# NES_IO_US_NOCUT_REV1_5.net
KiCad netlist of a schematic drawn in EAGLE
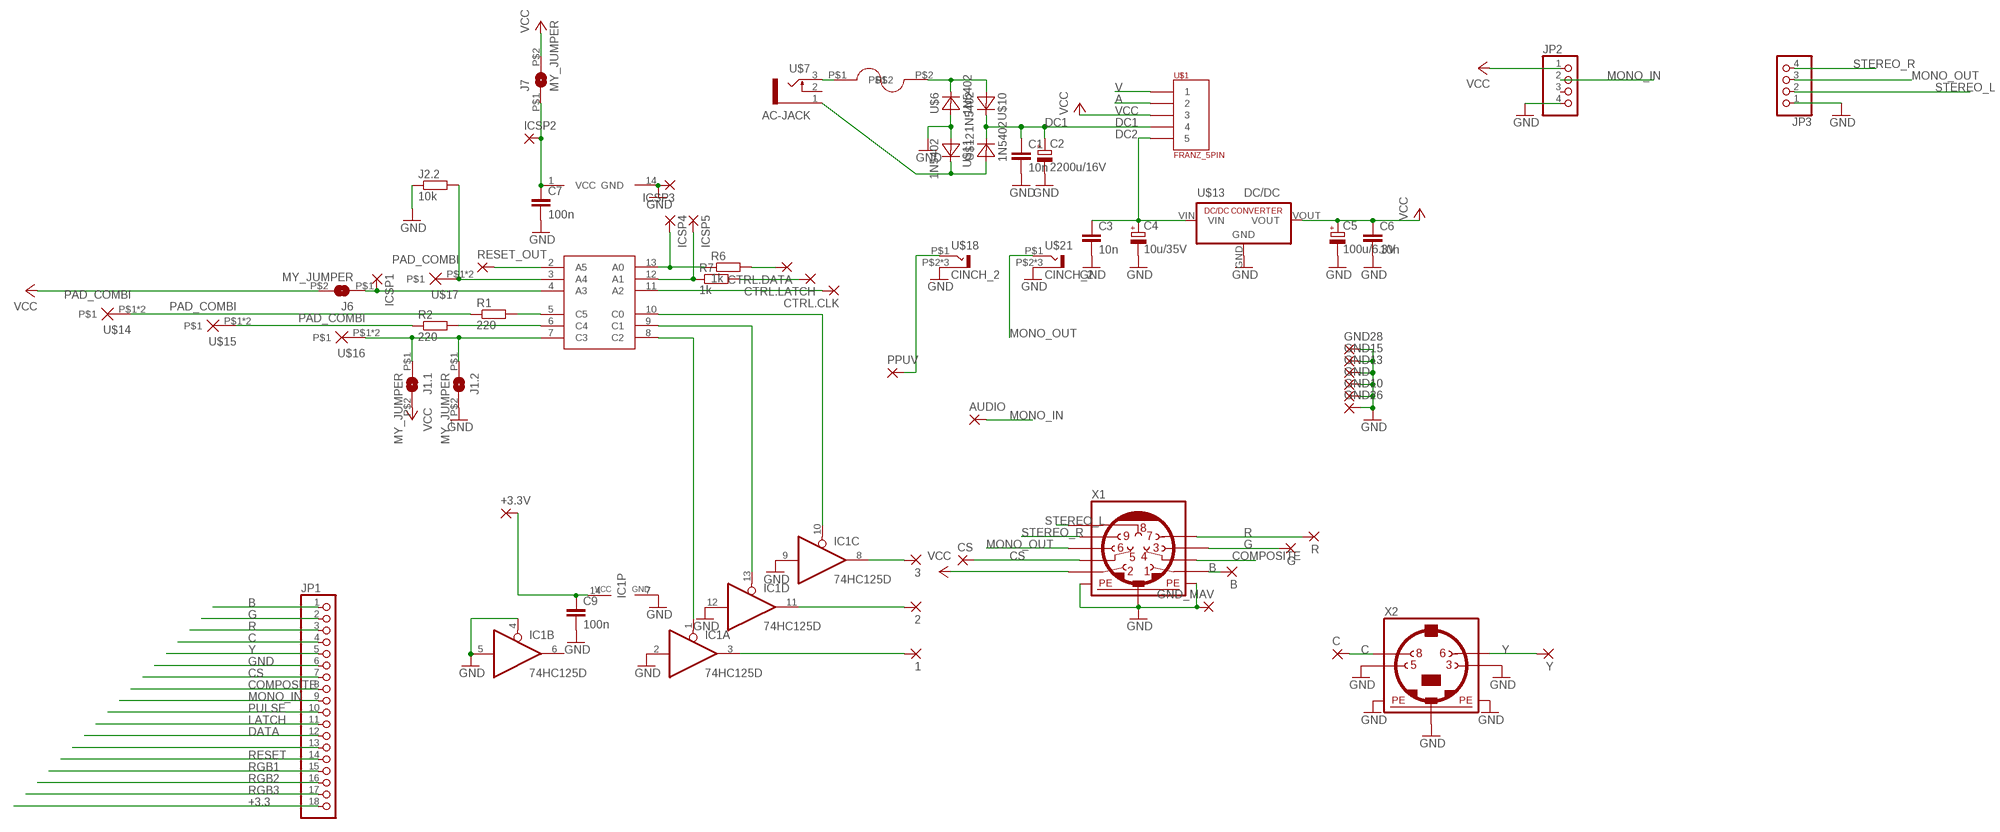
[diagram p0: schematic, sheet 1]

(export (version "E")
  (design (tool "Eeschema 10.0.6"))
  (components
    (comp (ref "+3.3V")
      (value "SMD2")
      (footprint "eagle-import:SMD1,27-2,54")
      (libsource (lib "eagle-import") (part "SMD2"))
    )
    (comp (ref "1")
      (value "SMD2")
      (footprint "eagle-import:SMD1,27-2,54")
      (libsource (lib "eagle-import") (part "SMD2"))
    )
    (comp (ref "2")
      (value "SMD2")
      (footprint "eagle-import:SMD1,27-2,54")
      (libsource (lib "eagle-import") (part "SMD2"))
    )
    (comp (ref "3")
      (value "SMD2")
      (footprint "eagle-import:SMD1,27-2,54")
      (libsource (lib "eagle-import") (part "SMD2"))
    )
    (comp (ref "AUDIO")
      (value "SMD2")
      (footprint "eagle-import:SMD1,27-2,54")
      (libsource (lib "eagle-import") (part "SMD2"))
    )
    (comp (ref "B")
      (value "SMD2")
      (footprint "eagle-import:SMD1,27-2,54")
      (libsource (lib "eagle-import") (part "SMD2"))
    )
    (comp (ref "C")
      (value "SMD2")
      (footprint "eagle-import:SMD1,27-2,54")
      (libsource (lib "eagle-import") (part "SMD2"))
    )
    (comp (ref "C1")
      (value "10n")
      (footprint "eagle-import:Z0805")
      (libsource (lib "eagle-import") (part "C0805"))
    )
    (comp (ref "C2")
      (value "2200u/16V")
      (footprint "eagle-import:E5-13")
      (libsource (lib "eagle-import") (part "resistor_CPOL-EUE5-13"))
    )
    (comp (ref "C3")
      (value "10n")
      (footprint "eagle-import:Z0805")
      (libsource (lib "eagle-import") (part "C0805"))
    )
    (comp (ref "C4")
      (value "10u/35V")
      (footprint "eagle-import:PANASONIC_B")
      (libsource (lib "eagle-import") (part "CPOL-EUB"))
    )
    (comp (ref "C5")
      (value "100u/6.3V")
      (footprint "eagle-import:PANASONIC_D")
      (libsource (lib "eagle-import") (part "CPOL-EUD"))
    )
    (comp (ref "C6")
      (value "10n")
      (footprint "eagle-import:Z0805")
      (libsource (lib "eagle-import") (part "C0805"))
    )
    (comp (ref "C7")
      (value "100n")
      (footprint "eagle-import:Z0805")
      (libsource (lib "eagle-import") (part "C0805"))
    )
    (comp (ref "C9")
      (value "100n")
      (footprint "eagle-import:Z0805")
      (libsource (lib "eagle-import") (part "C0805"))
    )
    (comp (ref "CS")
      (value "SMD2")
      (footprint "eagle-import:SMD1,27-2,54")
      (libsource (lib "eagle-import") (part "SMD2"))
    )
    (comp (ref "CTRL.CLK")
      (value "SMD2")
      (footprint "eagle-import:SMD1,27-2,54")
      (libsource (lib "eagle-import") (part "SMD2"))
    )
    (comp (ref "CTRL.DATA")
      (value "SMD2")
      (footprint "eagle-import:SMD1,27-2,54")
      (libsource (lib "eagle-import") (part "SMD2"))
    )
    (comp (ref "CTRL.LATCH")
      (value "SMD2")
      (footprint "eagle-import:SMD1,27-2,54")
      (libsource (lib "eagle-import") (part "SMD2"))
    )
    (comp (ref "G")
      (value "SMD2")
      (footprint "eagle-import:SMD1,27-2,54")
      (libsource (lib "eagle-import") (part "SMD2"))
    )
    (comp (ref "GND")
      (value "SMD5")
      (footprint "eagle-import:SMD2,54-5,08")
      (libsource (lib "eagle-import") (part "SMD5"))
    )
    (comp (ref "GND10")
      (value "SMD5")
      (footprint "eagle-import:SMD2,54-5,08")
      (libsource (lib "eagle-import") (part "SMD5"))
    )
    (comp (ref "GND13")
      (value "SMD5")
      (footprint "eagle-import:SMD2,54-5,08")
      (libsource (lib "eagle-import") (part "SMD5"))
    )
    (comp (ref "GND15")
      (value "SMD5")
      (footprint "eagle-import:SMD2,54-5,08")
      (libsource (lib "eagle-import") (part "SMD5"))
    )
    (comp (ref "GND26")
      (value "SMD5")
      (footprint "eagle-import:SMD2,54-5,08")
      (libsource (lib "eagle-import") (part "SMD5"))
    )
    (comp (ref "GND28")
      (value "SMD5")
      (footprint "eagle-import:SMD2,54-5,08")
      (libsource (lib "eagle-import") (part "SMD5"))
    )
    (comp (ref "GND_MAV")
      (value "SMD2")
      (footprint "eagle-import:SMD1,27-2,54")
      (libsource (lib "eagle-import") (part "SMD2"))
    )
    (comp (ref "IC1")
      (value "74HC125D")
      (footprint "eagle-import:SO14")
      (libsource (lib "eagle-import") (part "74125DHC"))
    )
    (comp (ref "ICSP1")
      (value "1,6/0,8")
      (footprint "eagle-import:1,6_0,8")
      (libsource (lib "eagle-import") (part "1,6/0,8"))
    )
    (comp (ref "ICSP2")
      (value "1,6/0,8")
      (footprint "eagle-import:1,6_0,8")
      (libsource (lib "eagle-import") (part "1,6/0,8"))
    )
    (comp (ref "ICSP3")
      (value "1,6/0,8")
      (footprint "eagle-import:1,6_0,8")
      (libsource (lib "eagle-import") (part "1,6/0,8"))
    )
    (comp (ref "ICSP4")
      (value "1,6/0,8")
      (footprint "eagle-import:1,6_0,8")
      (libsource (lib "eagle-import") (part "1,6/0,8"))
    )
    (comp (ref "ICSP5")
      (value "1,6/0,8")
      (footprint "eagle-import:1,6_0,8")
      (libsource (lib "eagle-import") (part "1,6/0,8"))
    )
    (comp (ref "J1.1")
      (value "MY_JUMPER")
      (footprint "eagle-import:MYJUMP")
      (libsource (lib "eagle-import") (part "MY_JUMPER"))
    )
    (comp (ref "J1.2")
      (value "MY_JUMPER")
      (footprint "eagle-import:MYJUMP")
      (libsource (lib "eagle-import") (part "MY_JUMPER"))
    )
    (comp (ref "J2.2")
      (value "10k")
      (footprint "eagle-import:Z0805")
      (libsource (lib "eagle-import") (part "R0805"))
    )
    (comp (ref "J6")
      (value "MY_JUMPER")
      (footprint "eagle-import:MYJUMP")
      (libsource (lib "eagle-import") (part "MY_JUMPER"))
    )
    (comp (ref "J7")
      (value "MY_JUMPER")
      (footprint "eagle-import:MYJUMP")
      (libsource (lib "eagle-import") (part "MY_JUMPER"))
    )
    (comp (ref "JP1")
      (value "PINHD-1X18_2.00")
      (footprint "eagle-import:1X18M")
      (libsource (lib "eagle-import") (part "PINHD-1X18_2.00"))
    )
    (comp (ref "JP2")
      (value "PINHD-1X04_2.54-S")
      (footprint "eagle-import:1X04-S")
      (libsource (lib "eagle-import") (part "PINHD-1X04_2.54-S"))
    )
    (comp (ref "JP3")
      (value "PINHD-1X04_2.54-S")
      (footprint "eagle-import:1X04-S")
      (libsource (lib "eagle-import") (part "PINHD-1X04_2.54-S"))
    )
    (comp (ref "PPUV")
      (value "SMD2")
      (footprint "eagle-import:SMD1,27-2,54")
      (libsource (lib "eagle-import") (part "SMD2"))
    )
    (comp (ref "R")
      (value "SMD2")
      (footprint "eagle-import:SMD1,27-2,54")
      (libsource (lib "eagle-import") (part "SMD2"))
    )
    (comp (ref "R1")
      (value "220")
      (footprint "eagle-import:Z0805")
      (libsource (lib "eagle-import") (part "R0805"))
    )
    (comp (ref "R2")
      (value "220")
      (footprint "eagle-import:Z0805")
      (libsource (lib "eagle-import") (part "R0805"))
    )
    (comp (ref "R6")
      (value "1k")
      (footprint "eagle-import:Z0805")
      (libsource (lib "eagle-import") (part "R0805"))
    )
    (comp (ref "R7")
      (value "1k")
      (footprint "eagle-import:Z0805")
      (libsource (lib "eagle-import") (part "R0805"))
    )
    (comp (ref "RESET_OUT")
      (value "SMD2")
      (footprint "eagle-import:SMD1,27-2,54")
      (libsource (lib "eagle-import") (part "SMD2"))
    )
    (comp (ref "U$1")
      (value "FRANZ_5PIN")
      (footprint "eagle-import:5X2.22RM4")
      (libsource (lib "eagle-import") (part "FRANZ_5PIN"))
    )
    (comp (ref "U$2")
      (value "FUSEHOLDER")
      (footprint "eagle-import:FUSEHOLDER")
      (libsource (lib "eagle-import") (part "FUSEHOLDER"))
    )
    (comp (ref "U$5")
      (value "PIC16F630_SIMPLE")
      (footprint "eagle-import:PIC16F630")
      (libsource (lib "eagle-import") (part "PIC16F630_SIMPLE"))
    )
    (comp (ref "U$6")
      (value "1N5402")
      (footprint "eagle-import:DO201")
      (libsource (lib "eagle-import") (part "1N5402"))
    )
    (comp (ref "U$7")
      (value "AC-JACK")
      (footprint "eagle-import:AC-JACK")
      (libsource (lib "eagle-import") (part "AC-JACK"))
    )
    (comp (ref "U$10")
      (value "1N5402")
      (footprint "eagle-import:DO201")
      (libsource (lib "eagle-import") (part "1N5402"))
    )
    (comp (ref "U$11")
      (value "1N5402")
      (footprint "eagle-import:DO201")
      (libsource (lib "eagle-import") (part "1N5402"))
    )
    (comp (ref "U$12")
      (value "1N5402")
      (footprint "eagle-import:DO201")
      (libsource (lib "eagle-import") (part "1N5402"))
    )
    (comp (ref "U$13")
      (value "DC/DC")
      (footprint "eagle-import:RECOM")
      (libsource (lib "eagle-import") (part "DC/DC"))
    )
    (comp (ref "U$14")
      (value "PAD_COMBI")
      (footprint "eagle-import:PAD_COMBI")
      (libsource (lib "eagle-import") (part "PAD_COMBI"))
    )
    (comp (ref "U$15")
      (value "PAD_COMBI")
      (footprint "eagle-import:PAD_COMBI")
      (libsource (lib "eagle-import") (part "PAD_COMBI"))
    )
    (comp (ref "U$16")
      (value "PAD_COMBI")
      (footprint "eagle-import:PAD_COMBI")
      (libsource (lib "eagle-import") (part "PAD_COMBI"))
    )
    (comp (ref "U$17")
      (value "PAD_COMBI")
      (footprint "eagle-import:PAD_COMBI")
      (libsource (lib "eagle-import") (part "PAD_COMBI"))
    )
    (comp (ref "U$18")
      (value "CINCH_2")
      (footprint "eagle-import:CINCH_2")
      (libsource (lib "eagle-import") (part "CINCH_2"))
    )
    (comp (ref "U$21")
      (value "CINCH_2")
      (footprint "eagle-import:CINCH_2")
      (libsource (lib "eagle-import") (part "CINCH_2"))
    )
    (comp (ref "X1")
      (value "MINI_DIN_9")
      (footprint "eagle-import:M_DIN9")
      (libsource (lib "eagle-import") (part "MINI_DIN_9"))
    )
    (comp (ref "X2")
      (value "MINI_DIN_4")
      (footprint "eagle-import:M_DIN4")
      (libsource (lib "eagle-import") (part "MINI_DIN_4"))
    )
    (comp (ref "Y")
      (value "SMD2")
      (footprint "eagle-import:SMD1,27-2,54")
      (libsource (lib "eagle-import") (part "SMD2"))
    )
  )
  (nets
    (net (code "1") (name "/+3.3") (class "Default")
      (node (ref "+3.3V") (pin "1") (pinfunction "P_1") (pintype "passive"))
      (node (ref "C9") (pin "1") (pinfunction "1_1") (pintype "passive"))
      (node (ref "IC1") (pin "14") (pinfunction "VCC_14") (pintype "power_in"))
      (node (ref "JP1") (pin "18") (pinfunction "18_18") (pintype "passive"))
    )
    (net (code "2") (name "/A") (class "Default")
      (node (ref "U$1") (pin "P$2") (pinfunction "2_P$2") (pintype "bidirectional"))
    )
    (net (code "3") (name "/B") (class "Default")
      (node (ref "B") (pin "1") (pinfunction "P_1") (pintype "passive"))
      (node (ref "JP1") (pin "1") (pinfunction "1_1") (pintype "passive"))
      (node (ref "X1") (pin "1") (pinfunction "1_1") (pintype "passive"))
    )
    (net (code "4") (name "/C") (class "Default")
      (node (ref "C") (pin "1") (pinfunction "P_1") (pintype "passive"))
      (node (ref "JP1") (pin "4") (pinfunction "4_4") (pintype "passive"))
      (node (ref "X2") (pin "8") (pinfunction "8_8") (pintype "passive"))
    )
    (net (code "5") (name "/COMPOSITE") (class "Default")
      (node (ref "JP1") (pin "8") (pinfunction "8_8") (pintype "passive"))
      (node (ref "PPUV") (pin "1") (pinfunction "P_1") (pintype "passive"))
      (node (ref "U$18") (pin "P$1") (pinfunction "T_P$1") (pintype "passive"))
      (node (ref "X1") (pin "4") (pinfunction "4_4") (pintype "passive"))
    )
    (net (code "6") (name "/CS") (class "Default")
      (node (ref "CS") (pin "1") (pinfunction "P_1") (pintype "passive"))
      (node (ref "JP1") (pin "7") (pinfunction "7_7") (pintype "passive"))
      (node (ref "X1") (pin "5") (pinfunction "5_5") (pintype "passive"))
    )
    (net (code "7") (name "/DATA") (class "Default")
      (node (ref "CTRL.DATA") (pin "1") (pinfunction "P_1") (pintype "passive"))
      (node (ref "JP1") (pin "12") (pinfunction "12_12") (pintype "passive"))
      (node (ref "R6") (pin "2") (pinfunction "2_2") (pintype "passive"))
    )
    (net (code "8") (name "/DC1") (class "Default")
      (node (ref "C1") (pin "1") (pinfunction "1_1") (pintype "passive"))
      (node (ref "C2") (pin "+") (pinfunction "+_+") (pintype "passive"))
      (node (ref "U$1") (pin "P$4") (pinfunction "4_P$4") (pintype "bidirectional"))
      (node (ref "U$10") (pin "C") (pinfunction "C_C") (pintype "passive"))
      (node (ref "U$12") (pin "C") (pinfunction "C_C") (pintype "passive"))
    )
    (net (code "9") (name "/DC2") (class "Default")
      (node (ref "C3") (pin "1") (pinfunction "1_1") (pintype "passive"))
      (node (ref "C4") (pin "+") (pinfunction "+_+") (pintype "passive"))
      (node (ref "U$1") (pin "P$5") (pinfunction "5_P$5") (pintype "bidirectional"))
      (node (ref "U$13") (pin "VIN") (pinfunction "VIN_VIN") (pintype "passive"))
    )
    (net (code "10") (name "/G") (class "Default")
      (node (ref "G") (pin "1") (pinfunction "P_1") (pintype "passive"))
      (node (ref "JP1") (pin "2") (pinfunction "2_2") (pintype "passive"))
      (node (ref "X1") (pin "3") (pinfunction "3_3") (pintype "passive"))
    )
    (net (code "11") (name "/LATCH") (class "Default")
      (node (ref "CTRL.LATCH") (pin "1") (pinfunction "P_1") (pintype "passive"))
      (node (ref "JP1") (pin "11") (pinfunction "11_11") (pintype "passive"))
      (node (ref "R7") (pin "2") (pinfunction "2_2") (pintype "passive"))
    )
    (net (code "12") (name "/MONO_IN") (class "Default")
      (node (ref "AUDIO") (pin "1") (pinfunction "P_1") (pintype "passive"))
      (node (ref "JP1") (pin "9") (pinfunction "9_9") (pintype "passive"))
      (node (ref "JP2") (pin "2") (pinfunction "2_2") (pintype "passive"))
    )
    (net (code "13") (name "/MONO_OUT") (class "Default")
      (node (ref "JP3") (pin "3") (pinfunction "3_3") (pintype "passive"))
      (node (ref "U$21") (pin "P$1") (pinfunction "T_P$1") (pintype "passive"))
      (node (ref "X1") (pin "6") (pinfunction "6_6") (pintype "passive"))
    )
    (net (code "14") (name "/PULSE") (class "Default")
      (node (ref "CTRL.CLK") (pin "1") (pinfunction "P_1") (pintype "passive"))
      (node (ref "JP1") (pin "10") (pinfunction "10_10") (pintype "passive"))
      (node (ref "U$5") (pin "11") (pinfunction "A2_11") (pintype "bidirectional"))
    )
    (net (code "15") (name "/R") (class "Default")
      (node (ref "JP1") (pin "3") (pinfunction "3_3") (pintype "passive"))
      (node (ref "R") (pin "1") (pinfunction "P_1") (pintype "passive"))
      (node (ref "X1") (pin "7") (pinfunction "7_7") (pintype "passive"))
    )
    (net (code "16") (name "/RESET") (class "Default")
      (node (ref "JP1") (pin "14") (pinfunction "14_14") (pintype "passive"))
      (node (ref "RESET_OUT") (pin "1") (pinfunction "P_1") (pintype "passive"))
      (node (ref "U$5") (pin "2") (pinfunction "A5_2") (pintype "bidirectional"))
    )
    (net (code "17") (name "/RGB1") (class "Default")
      (node (ref "3") (pin "1") (pinfunction "P_1") (pintype "passive"))
      (node (ref "IC1") (pin "8") (pinfunction "O_8") (pintype "tri_state"))
      (node (ref "JP1") (pin "15") (pinfunction "15_15") (pintype "passive"))
    )
    (net (code "18") (name "/RGB2") (class "Default")
      (node (ref "2") (pin "1") (pinfunction "P_1") (pintype "passive"))
      (node (ref "IC1") (pin "11") (pinfunction "O_11") (pintype "tri_state"))
      (node (ref "JP1") (pin "16") (pinfunction "16_16") (pintype "passive"))
    )
    (net (code "19") (name "/RGB3") (class "Default")
      (node (ref "1") (pin "1") (pinfunction "P_1") (pintype "passive"))
      (node (ref "IC1") (pin "3") (pinfunction "O_3") (pintype "tri_state"))
      (node (ref "JP1") (pin "17") (pinfunction "17_17") (pintype "passive"))
    )
    (net (code "20") (name "/STEREO_L") (class "Default")
      (node (ref "JP3") (pin "2") (pinfunction "2_2") (pintype "passive"))
      (node (ref "X1") (pin "8") (pinfunction "8_8") (pintype "passive"))
    )
    (net (code "21") (name "/STEREO_R") (class "Default")
      (node (ref "JP3") (pin "4") (pinfunction "4_4") (pintype "passive"))
      (node (ref "X1") (pin "9") (pinfunction "9_9") (pintype "passive"))
    )
    (net (code "22") (name "/V") (class "Default")
      (node (ref "U$1") (pin "P$1") (pinfunction "1_P$1") (pintype "bidirectional"))
    )
    (net (code "23") (name "/Y") (class "Default")
      (node (ref "JP1") (pin "5") (pinfunction "5_5") (pintype "passive"))
      (node (ref "X2") (pin "6") (pinfunction "6_6") (pintype "passive"))
      (node (ref "Y") (pin "1") (pinfunction "P_1") (pintype "passive"))
    )
    (net (code "24") (name "GND") (class "Default")
      (node (ref "C1") (pin "2") (pinfunction "2_2") (pintype "passive"))
      (node (ref "C2") (pin "-") (pinfunction "-_-") (pintype "passive"))
      (node (ref "C3") (pin "2") (pinfunction "2_2") (pintype "passive"))
      (node (ref "C4") (pin "-") (pinfunction "-_-") (pintype "passive"))
      (node (ref "C5") (pin "-") (pinfunction "-_-") (pintype "passive"))
      (node (ref "C6") (pin "2") (pinfunction "2_2") (pintype "passive"))
      (node (ref "C7") (pin "2") (pinfunction "2_2") (pintype "passive"))
      (node (ref "C9") (pin "2") (pinfunction "2_2") (pintype "passive"))
      (node (ref "GND") (pin "1") (pinfunction "P_1") (pintype "passive"))
      (node (ref "GND10") (pin "1") (pinfunction "P_1") (pintype "passive"))
      (node (ref "GND13") (pin "1") (pinfunction "P_1") (pintype "passive"))
      (node (ref "GND15") (pin "1") (pinfunction "P_1") (pintype "passive"))
      (node (ref "GND26") (pin "1") (pinfunction "P_1") (pintype "passive"))
      (node (ref "GND28") (pin "1") (pinfunction "P_1") (pintype "passive"))
      (node (ref "GND_MAV") (pin "1") (pinfunction "P_1") (pintype "passive"))
      (node (ref "IC1") (pin "12") (pinfunction "I_12") (pintype "input"))
      (node (ref "IC1") (pin "2") (pinfunction "I_2") (pintype "input"))
      (node (ref "IC1") (pin "4") (pinfunction "OE_4") (pintype "input"))
      (node (ref "IC1") (pin "5") (pinfunction "I_5") (pintype "input"))
      (node (ref "IC1") (pin "7") (pinfunction "GND_7") (pintype "power_in"))
      (node (ref "IC1") (pin "9") (pinfunction "I_9") (pintype "input"))
      (node (ref "ICSP3") (pin "1") (pinfunction "P_1") (pintype "passive"))
      (node (ref "J1.2") (pin "P$2") (pinfunction "2_P$2") (pintype "passive"))
      (node (ref "J2.2") (pin "1") (pinfunction "1_1") (pintype "passive"))
      (node (ref "JP1") (pin "6") (pinfunction "6_6") (pintype "passive"))
      (node (ref "JP2") (pin "4") (pinfunction "4_4") (pintype "passive"))
      (node (ref "JP3") (pin "1") (pinfunction "1_1") (pintype "passive"))
      (node (ref "U$11") (pin "A") (pinfunction "A_A") (pintype "passive"))
      (node (ref "U$13") (pin "GND") (pinfunction "GND_GND") (pintype "passive"))
      (node (ref "U$18") (pin "P$2") (pinfunction "S_P$2") (pintype "passive"))
      (node (ref "U$18") (pin "P$3") (pinfunction "S_P$3") (pintype "passive"))
      (node (ref "U$18") (pin "P$4") (pinfunction "S_P$4") (pintype "passive"))
      (node (ref "U$21") (pin "P$2") (pinfunction "S_P$2") (pintype "passive"))
      (node (ref "U$21") (pin "P$3") (pinfunction "S_P$3") (pintype "passive"))
      (node (ref "U$21") (pin "P$4") (pinfunction "S_P$4") (pintype "passive"))
      (node (ref "U$5") (pin "14") (pinfunction "GND_14") (pintype "bidirectional"))
      (node (ref "U$6") (pin "A") (pinfunction "A_A") (pintype "passive"))
      (node (ref "X1") (pin "SH1") (pinfunction "PE1_SH1") (pintype "power_in"))
      (node (ref "X1") (pin "SH2") (pinfunction "PE2_SH2") (pintype "power_in"))
      (node (ref "X1") (pin "SH3") (pinfunction "PE3_SH3") (pintype "power_in"))
      (node (ref "X2") (pin "3") (pinfunction "3_3") (pintype "passive"))
      (node (ref "X2") (pin "5") (pinfunction "5_5") (pintype "passive"))
      (node (ref "X2") (pin "SH1") (pinfunction "PE1_SH1") (pintype "power_in"))
      (node (ref "X2") (pin "SH2") (pinfunction "PE2_SH2") (pintype "power_in"))
      (node (ref "X2") (pin "SH3") (pinfunction "PE3_SH3") (pintype "power_in"))
    )
    (net (code "25") (name "Net-(IC1A-OE)") (class "Default")
      (node (ref "IC1") (pin "1") (pinfunction "OE_1") (pintype "input"))
      (node (ref "U$5") (pin "8") (pinfunction "C2_8") (pintype "bidirectional"))
    )
    (net (code "26") (name "Net-(IC1C-OE)") (class "Default")
      (node (ref "IC1") (pin "10") (pinfunction "OE_10") (pintype "input"))
      (node (ref "U$5") (pin "10") (pinfunction "C0_10") (pintype "bidirectional"))
    )
    (net (code "27") (name "Net-(IC1D-OE)") (class "Default")
      (node (ref "IC1") (pin "13") (pinfunction "OE_13") (pintype "input"))
      (node (ref "U$5") (pin "9") (pinfunction "C1_9") (pintype "bidirectional"))
    )
    (net (code "28") (name "Net-(ICSP1-P)") (class "Default")
      (node (ref "ICSP1") (pin "1") (pinfunction "P_1") (pintype "passive"))
      (node (ref "J6") (pin "P$1") (pinfunction "1_P$1") (pintype "passive"))
      (node (ref "U$5") (pin "4") (pinfunction "A3_4") (pintype "bidirectional"))
    )
    (net (code "29") (name "Net-(ICSP2-P)") (class "Default")
      (node (ref "C7") (pin "1") (pinfunction "1_1") (pintype "passive"))
      (node (ref "ICSP2") (pin "1") (pinfunction "P_1") (pintype "passive"))
      (node (ref "J7") (pin "P$1") (pinfunction "1_P$1") (pintype "passive"))
      (node (ref "U$5") (pin "1") (pinfunction "VCC_1") (pintype "bidirectional"))
    )
    (net (code "30") (name "Net-(ICSP4-P)") (class "Default")
      (node (ref "ICSP4") (pin "1") (pinfunction "P_1") (pintype "passive"))
      (node (ref "R6") (pin "1") (pinfunction "1_1") (pintype "passive"))
      (node (ref "U$5") (pin "13") (pinfunction "A0_13") (pintype "bidirectional"))
    )
    (net (code "31") (name "Net-(ICSP5-P)") (class "Default")
      (node (ref "ICSP5") (pin "1") (pinfunction "P_1") (pintype "passive"))
      (node (ref "R7") (pin "1") (pinfunction "1_1") (pintype "passive"))
      (node (ref "U$5") (pin "12") (pinfunction "A1_12") (pintype "bidirectional"))
    )
    (net (code "32") (name "Net-(J1.1-1)") (class "Default")
      (node (ref "J1.1") (pin "P$1") (pinfunction "1_P$1") (pintype "passive"))
      (node (ref "J1.2") (pin "P$1") (pinfunction "1_P$1") (pintype "passive"))
      (node (ref "U$16") (pin "P$1") (pinfunction "P$1_P$1") (pintype "bidirectional"))
      (node (ref "U$16") (pin "P$2") (pinfunction "P$1_P$2") (pintype "bidirectional"))
      (node (ref "U$5") (pin "7") (pinfunction "C3_7") (pintype "bidirectional"))
    )
    (net (code "33") (name "Net-(R1-Pad1)") (class "Default")
      (node (ref "R1") (pin "1") (pinfunction "1_1") (pintype "passive"))
      (node (ref "U$14") (pin "P$1") (pinfunction "P$1_P$1") (pintype "bidirectional"))
      (node (ref "U$14") (pin "P$2") (pinfunction "P$1_P$2") (pintype "bidirectional"))
    )
    (net (code "34") (name "Net-(R2-Pad1)") (class "Default")
      (node (ref "R2") (pin "1") (pinfunction "1_1") (pintype "passive"))
      (node (ref "U$15") (pin "P$1") (pinfunction "P$1_P$1") (pintype "bidirectional"))
      (node (ref "U$15") (pin "P$2") (pinfunction "P$1_P$2") (pintype "bidirectional"))
    )
    (net (code "35") (name "Net-(U$2-PadP$1)") (class "Default")
      (node (ref "U$2") (pin "P$1") (pinfunction "P$1_P$1") (pintype "bidirectional"))
      (node (ref "U$7") (pin "3") (pinfunction "3_3") (pintype "passive"))
    )
    (net (code "36") (name "Net-(U$5A-A4)") (class "Default")
      (node (ref "J2.2") (pin "2") (pinfunction "2_2") (pintype "passive"))
      (node (ref "U$17") (pin "P$1") (pinfunction "P$1_P$1") (pintype "bidirectional"))
      (node (ref "U$17") (pin "P$2") (pinfunction "P$1_P$2") (pintype "bidirectional"))
      (node (ref "U$5") (pin "3") (pinfunction "A4_3") (pintype "bidirectional"))
    )
    (net (code "37") (name "Net-(U$5A-C4)") (class "Default")
      (node (ref "R2") (pin "2") (pinfunction "2_2") (pintype "passive"))
      (node (ref "U$5") (pin "6") (pinfunction "C4_6") (pintype "bidirectional"))
    )
    (net (code "38") (name "Net-(U$5A-C5)") (class "Default")
      (node (ref "R1") (pin "2") (pinfunction "2_2") (pintype "passive"))
      (node (ref "U$5") (pin "5") (pinfunction "C5_5") (pintype "bidirectional"))
    )
    (net (code "39") (name "Net-(U$7-5)") (class "Default")
      (node (ref "U$11") (pin "C") (pinfunction "C_C") (pintype "passive"))
      (node (ref "U$12") (pin "A") (pinfunction "A_A") (pintype "passive"))
      (node (ref "U$7") (pin "1") (pinfunction "5_1") (pintype "passive"))
    )
    (net (code "40") (name "Net-(U$10-PadA)") (class "Default")
      (node (ref "U$10") (pin "A") (pinfunction "A_A") (pintype "passive"))
      (node (ref "U$2") (pin "P$2") (pinfunction "P$2_P$2") (pintype "bidirectional"))
      (node (ref "U$6") (pin "C") (pinfunction "C_C") (pintype "passive"))
    )
    (net (code "41") (name "VCC") (class "Default")
      (node (ref "C5") (pin "+") (pinfunction "+_+") (pintype "passive"))
      (node (ref "C6") (pin "1") (pinfunction "1_1") (pintype "passive"))
      (node (ref "J1.1") (pin "P$2") (pinfunction "2_P$2") (pintype "passive"))
      (node (ref "J6") (pin "P$2") (pinfunction "2_P$2") (pintype "passive"))
      (node (ref "J7") (pin "P$2") (pinfunction "2_P$2") (pintype "passive"))
      (node (ref "JP2") (pin "1") (pinfunction "1_1") (pintype "passive"))
      (node (ref "U$1") (pin "P$3") (pinfunction "3_P$3") (pintype "bidirectional"))
      (node (ref "U$13") (pin "VOUT") (pinfunction "VOUT_VOUT") (pintype "passive"))
      (node (ref "X1") (pin "2") (pinfunction "2_2") (pintype "passive"))
    )
    (net (code "42") (name "unconnected-(IC1B-O-Pad6)") (class "Default")
      (node (ref "IC1") (pin "6") (pinfunction "O_6") (pintype "tri_state"))
    )
    (net (code "43") (name "unconnected-(JP1-Pad13)") (class "Default")
      (node (ref "JP1") (pin "13") (pinfunction "13_13") (pintype "passive"))
    )
    (net (code "44") (name "unconnected-(JP2-Pad3)") (class "Default")
      (node (ref "JP2") (pin "3") (pinfunction "3_3") (pintype "passive"))
    )
    (net (code "45") (name "unconnected-(U$7-4-Pad2)") (class "Default")
      (node (ref "U$7") (pin "2") (pinfunction "4_2") (pintype "passive"))
    )
  )
)
